# Sheet1.net
KiCad netlist of a schematic drawn in Altium Designer
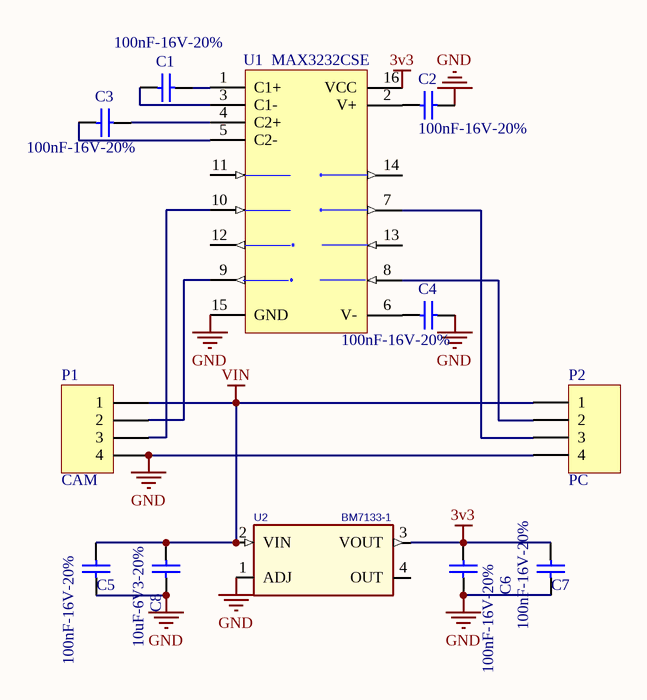
[diagram p0: Sheet1.SchDoc]

(export (version "E")
  (design (tool "Eeschema 10.0.6"))
  (components
    (comp (ref "C1")
      (value "100nF-16V-20%")
      (footprint "C0603")
      (description "CAP CER 0.1UF 16V Y5V 0603")
      (fields
        (field (name "MANUFACTURER") "Yageo")
        (field (name "DIGI-KEY PART NUMBER") "311-1369-1-ND")
        (field (name "PUBLISHER") "Altium Limited")
      )
      (libsource (lib "Miscellaneous Devices") (part "Cap"))
    )
    (comp (ref "C2")
      (value "100nF-16V-20%")
      (footprint "C0603")
      (description "CAP CER 0.1UF 16V Y5V 0603")
      (fields
        (field (name "MANUFACTURER") "Yageo")
        (field (name "DIGI-KEY PART NUMBER") "311-1369-1-ND")
        (field (name "PUBLISHER") "Altium Limited")
      )
      (libsource (lib "Miscellaneous Devices") (part "Cap"))
    )
    (comp (ref "C3")
      (value "100nF-16V-20%")
      (footprint "C0603")
      (description "CAP CER 0.1UF 16V Y5V 0603")
      (fields
        (field (name "MANUFACTURER") "Yageo")
        (field (name "DIGI-KEY PART NUMBER") "311-1369-1-ND")
        (field (name "PUBLISHER") "Altium Limited")
      )
      (libsource (lib "Miscellaneous Devices") (part "Cap"))
    )
    (comp (ref "C4")
      (value "100nF-16V-20%")
      (footprint "C0603")
      (description "CAP CER 0.1UF 16V Y5V 0603")
      (fields
        (field (name "MANUFACTURER") "Yageo")
        (field (name "DIGI-KEY PART NUMBER") "311-1369-1-ND")
        (field (name "PUBLISHER") "Altium Limited")
      )
      (libsource (lib "Miscellaneous Devices") (part "Cap"))
    )
    (comp (ref "C5")
      (value "100nF-16V-20%")
      (footprint "C0603")
      (description "CAP CER 0.1UF 16V Y5V 0603")
      (fields
        (field (name "MANUFACTURER") "Yageo")
        (field (name "DIGI-KEY PART NUMBER") "311-1369-1-ND")
        (field (name "PUBLISHER") "Altium Limited")
      )
      (libsource (lib "Miscellaneous Devices") (part "Cap"))
    )
    (comp (ref "C6")
      (value "100nF-16V-20%")
      (footprint "C0603")
      (description "CAP CER 0.1UF 16V Y5V 0603")
      (fields
        (field (name "MANUFACTURER") "Yageo")
        (field (name "DIGI-KEY PART NUMBER") "311-1369-1-ND")
        (field (name "PUBLISHER") "Altium Limited")
      )
      (libsource (lib "Miscellaneous Devices") (part "Cap"))
    )
    (comp (ref "C7")
      (value "100nF-16V-20%")
      (footprint "C0603")
      (description "CAP CER 0.1UF 16V Y5V 0603")
      (fields
        (field (name "MANUFACTURER") "Yageo")
        (field (name "DIGI-KEY PART NUMBER") "311-1369-1-ND")
        (field (name "PUBLISHER") "Altium Limited")
      )
      (libsource (lib "Miscellaneous Devices") (part "Cap"))
    )
    (comp (ref "C8")
      (value "10uF-6V3-20%")
      (footprint "C0603")
      (description "CAP CER 10UF 6.3V 20% X5R 0603")
      (fields
        (field (name "MANUFACTURER") "Yageo")
        (field (name "DIGI-KEY PART NUMBER") "311-1448-1-ND")
        (field (name "PUBLISHER") "Altium Limited")
      )
      (libsource (lib "Miscellaneous Devices") (part "Cap"))
    )
    (comp (ref "P1")
      (value "CAM")
      (footprint "Header-2mm-4pin")
      (description "Header, 4-Pin")
      (fields (field (name "PUBLISHER") "Altium Limited"))
      (libsource (lib "") (part "MHDR1X4_1"))
    )
    (comp (ref "P2")
      (value "PC")
      (footprint "Header-2mm-4pin")
      (description "Header, 4-Pin")
      (fields (field (name "PUBLISHER") "Altium Limited"))
      (libsource (lib "Miscellaneous Connectors") (part "MHDR1X4"))
    )
    (comp (ref "U1")
      (value "MAX3232CSE")
      (footprint "SO16-150mil")
      (description "3.0V TO 5.5V, Low-Power, up to 1Mbps, True RS-232 Transceiver Using Four 0.1µF External Capacitor")
      (fields (field (name "PUBLISHER") "Altium Limited"))
      (libsource (lib "Maxim Communication Transceiver") (part "MAX3232CSE"))
    )
    (comp (ref "U2") (value "BM7133-1") (footprint "SOT_89") (libsource (lib "*") (part "LM117_0")))
  )
  (nets
    (net (code "1") (name "3v3") (class "Default")
      (node (ref "C6") (pin "2") (pinfunction "2_2") (pintype "passive"))
      (node (ref "C7") (pin "1") (pinfunction "1_1") (pintype "passive"))
      (node (ref "U1") (pin "16") (pinfunction "VCC_16") (pintype "power_in"))
      (node (ref "U2") (pin "3") (pinfunction "VOUT_3") (pintype "output"))
    )
    (net (code "2") (name "GND") (class "Default")
      (node (ref "C2") (pin "2") (pinfunction "2_2") (pintype "passive"))
      (node (ref "C4") (pin "2") (pinfunction "2_2") (pintype "passive"))
      (node (ref "C5") (pin "2") (pinfunction "2_2") (pintype "passive"))
      (node (ref "C6") (pin "1") (pinfunction "1_1") (pintype "passive"))
      (node (ref "C7") (pin "2") (pinfunction "2_2") (pintype "passive"))
      (node (ref "C8") (pin "1") (pinfunction "1_1") (pintype "passive"))
      (node (ref "P1") (pin "4") (pinfunction "4_4") (pintype "passive"))
      (node (ref "P2") (pin "4") (pinfunction "4_4") (pintype "passive"))
      (node (ref "U1") (pin "15") (pinfunction "GND_15") (pintype "power_in"))
      (node (ref "U2") (pin "1") (pinfunction "ADJ_1") (pintype "passive"))
    )
    (net (code "3") (name "Net-(U1-C1+)") (class "Default")
      (node (ref "C1") (pin "2") (pinfunction "2_2") (pintype "passive"))
      (node (ref "U1") (pin "1") (pinfunction "C1+_1") (pintype "passive"))
    )
    (net (code "4") (name "Net-(U1-C1-)") (class "Default")
      (node (ref "C1") (pin "1") (pinfunction "1_1") (pintype "passive"))
      (node (ref "U1") (pin "3") (pinfunction "C1-_3") (pintype "passive"))
    )
    (net (code "5") (name "Net-(U1-C2+)") (class "Default")
      (node (ref "C3") (pin "2") (pinfunction "2_2") (pintype "passive"))
      (node (ref "U1") (pin "4") (pinfunction "C2+_4") (pintype "passive"))
    )
    (net (code "6") (name "Net-(U1-C2-)") (class "Default")
      (node (ref "C3") (pin "1") (pinfunction "1_1") (pintype "passive"))
      (node (ref "U1") (pin "5") (pinfunction "C2-_5") (pintype "passive"))
    )
    (net (code "7") (name "Net-(U1-R2IN)") (class "Default")
      (node (ref "P2") (pin "2") (pinfunction "2_2") (pintype "passive"))
      (node (ref "U1") (pin "8") (pinfunction "R2IN_8") (pintype "input"))
    )
    (net (code "8") (name "Net-(U1-R2OUT)") (class "Default")
      (node (ref "P1") (pin "2") (pinfunction "2_2") (pintype "passive"))
      (node (ref "U1") (pin "9") (pinfunction "R2OUT_9") (pintype "output"))
    )
    (net (code "9") (name "Net-(U1-T2IN)") (class "Default")
      (node (ref "P1") (pin "3") (pinfunction "3_3") (pintype "passive"))
      (node (ref "U1") (pin "10") (pinfunction "T2IN_10") (pintype "input"))
    )
    (net (code "10") (name "Net-(U1-T2OUT)") (class "Default")
      (node (ref "P2") (pin "3") (pinfunction "3_3") (pintype "passive"))
      (node (ref "U1") (pin "7") (pinfunction "T2OUT_7") (pintype "output"))
    )
    (net (code "11") (name "Net-(U1-V+)") (class "Default")
      (node (ref "C2") (pin "1") (pinfunction "1_1") (pintype "passive"))
      (node (ref "U1") (pin "2") (pinfunction "V+_2") (pintype "power_in"))
    )
    (net (code "12") (name "Net-(U1-V-)") (class "Default")
      (node (ref "C4") (pin "1") (pinfunction "1_1") (pintype "passive"))
      (node (ref "U1") (pin "6") (pinfunction "V-_6") (pintype "power_in"))
    )
    (net (code "13") (name "VIN") (class "Default")
      (node (ref "C5") (pin "1") (pinfunction "1_1") (pintype "passive"))
      (node (ref "C8") (pin "2") (pinfunction "2_2") (pintype "passive"))
      (node (ref "P1") (pin "1") (pinfunction "1_1") (pintype "passive"))
      (node (ref "P2") (pin "1") (pinfunction "1_1") (pintype "passive"))
      (node (ref "U2") (pin "2") (pinfunction "VIN_2") (pintype "input"))
    )
    (net (code "14") (name "unconnected-(U1-R1IN-Pad13)") (class "Default")
      (node (ref "U1") (pin "13") (pinfunction "R1IN_13") (pintype "input"))
    )
    (net (code "15") (name "unconnected-(U1-R1OUT-Pad12)") (class "Default")
      (node (ref "U1") (pin "12") (pinfunction "R1OUT_12") (pintype "output"))
    )
    (net (code "16") (name "unconnected-(U1-T1IN-Pad11)") (class "Default")
      (node (ref "U1") (pin "11") (pinfunction "T1IN_11") (pintype "input"))
    )
    (net (code "17") (name "unconnected-(U1-T1OUT-Pad14)") (class "Default")
      (node (ref "U1") (pin "14") (pinfunction "T1OUT_14") (pintype "output"))
    )
    (net (code "18") (name "unconnected-(U2-OUT-Pad4)") (class "Default")
      (node (ref "U2") (pin "4") (pinfunction "OUT_4") (pintype "passive"))
    )
  )
)
